# EasyEDA_SCH_5_5-OLED-to-RP5-MIPI-HAT.net
KiCad netlist of a schematic drawn in EasyEDA
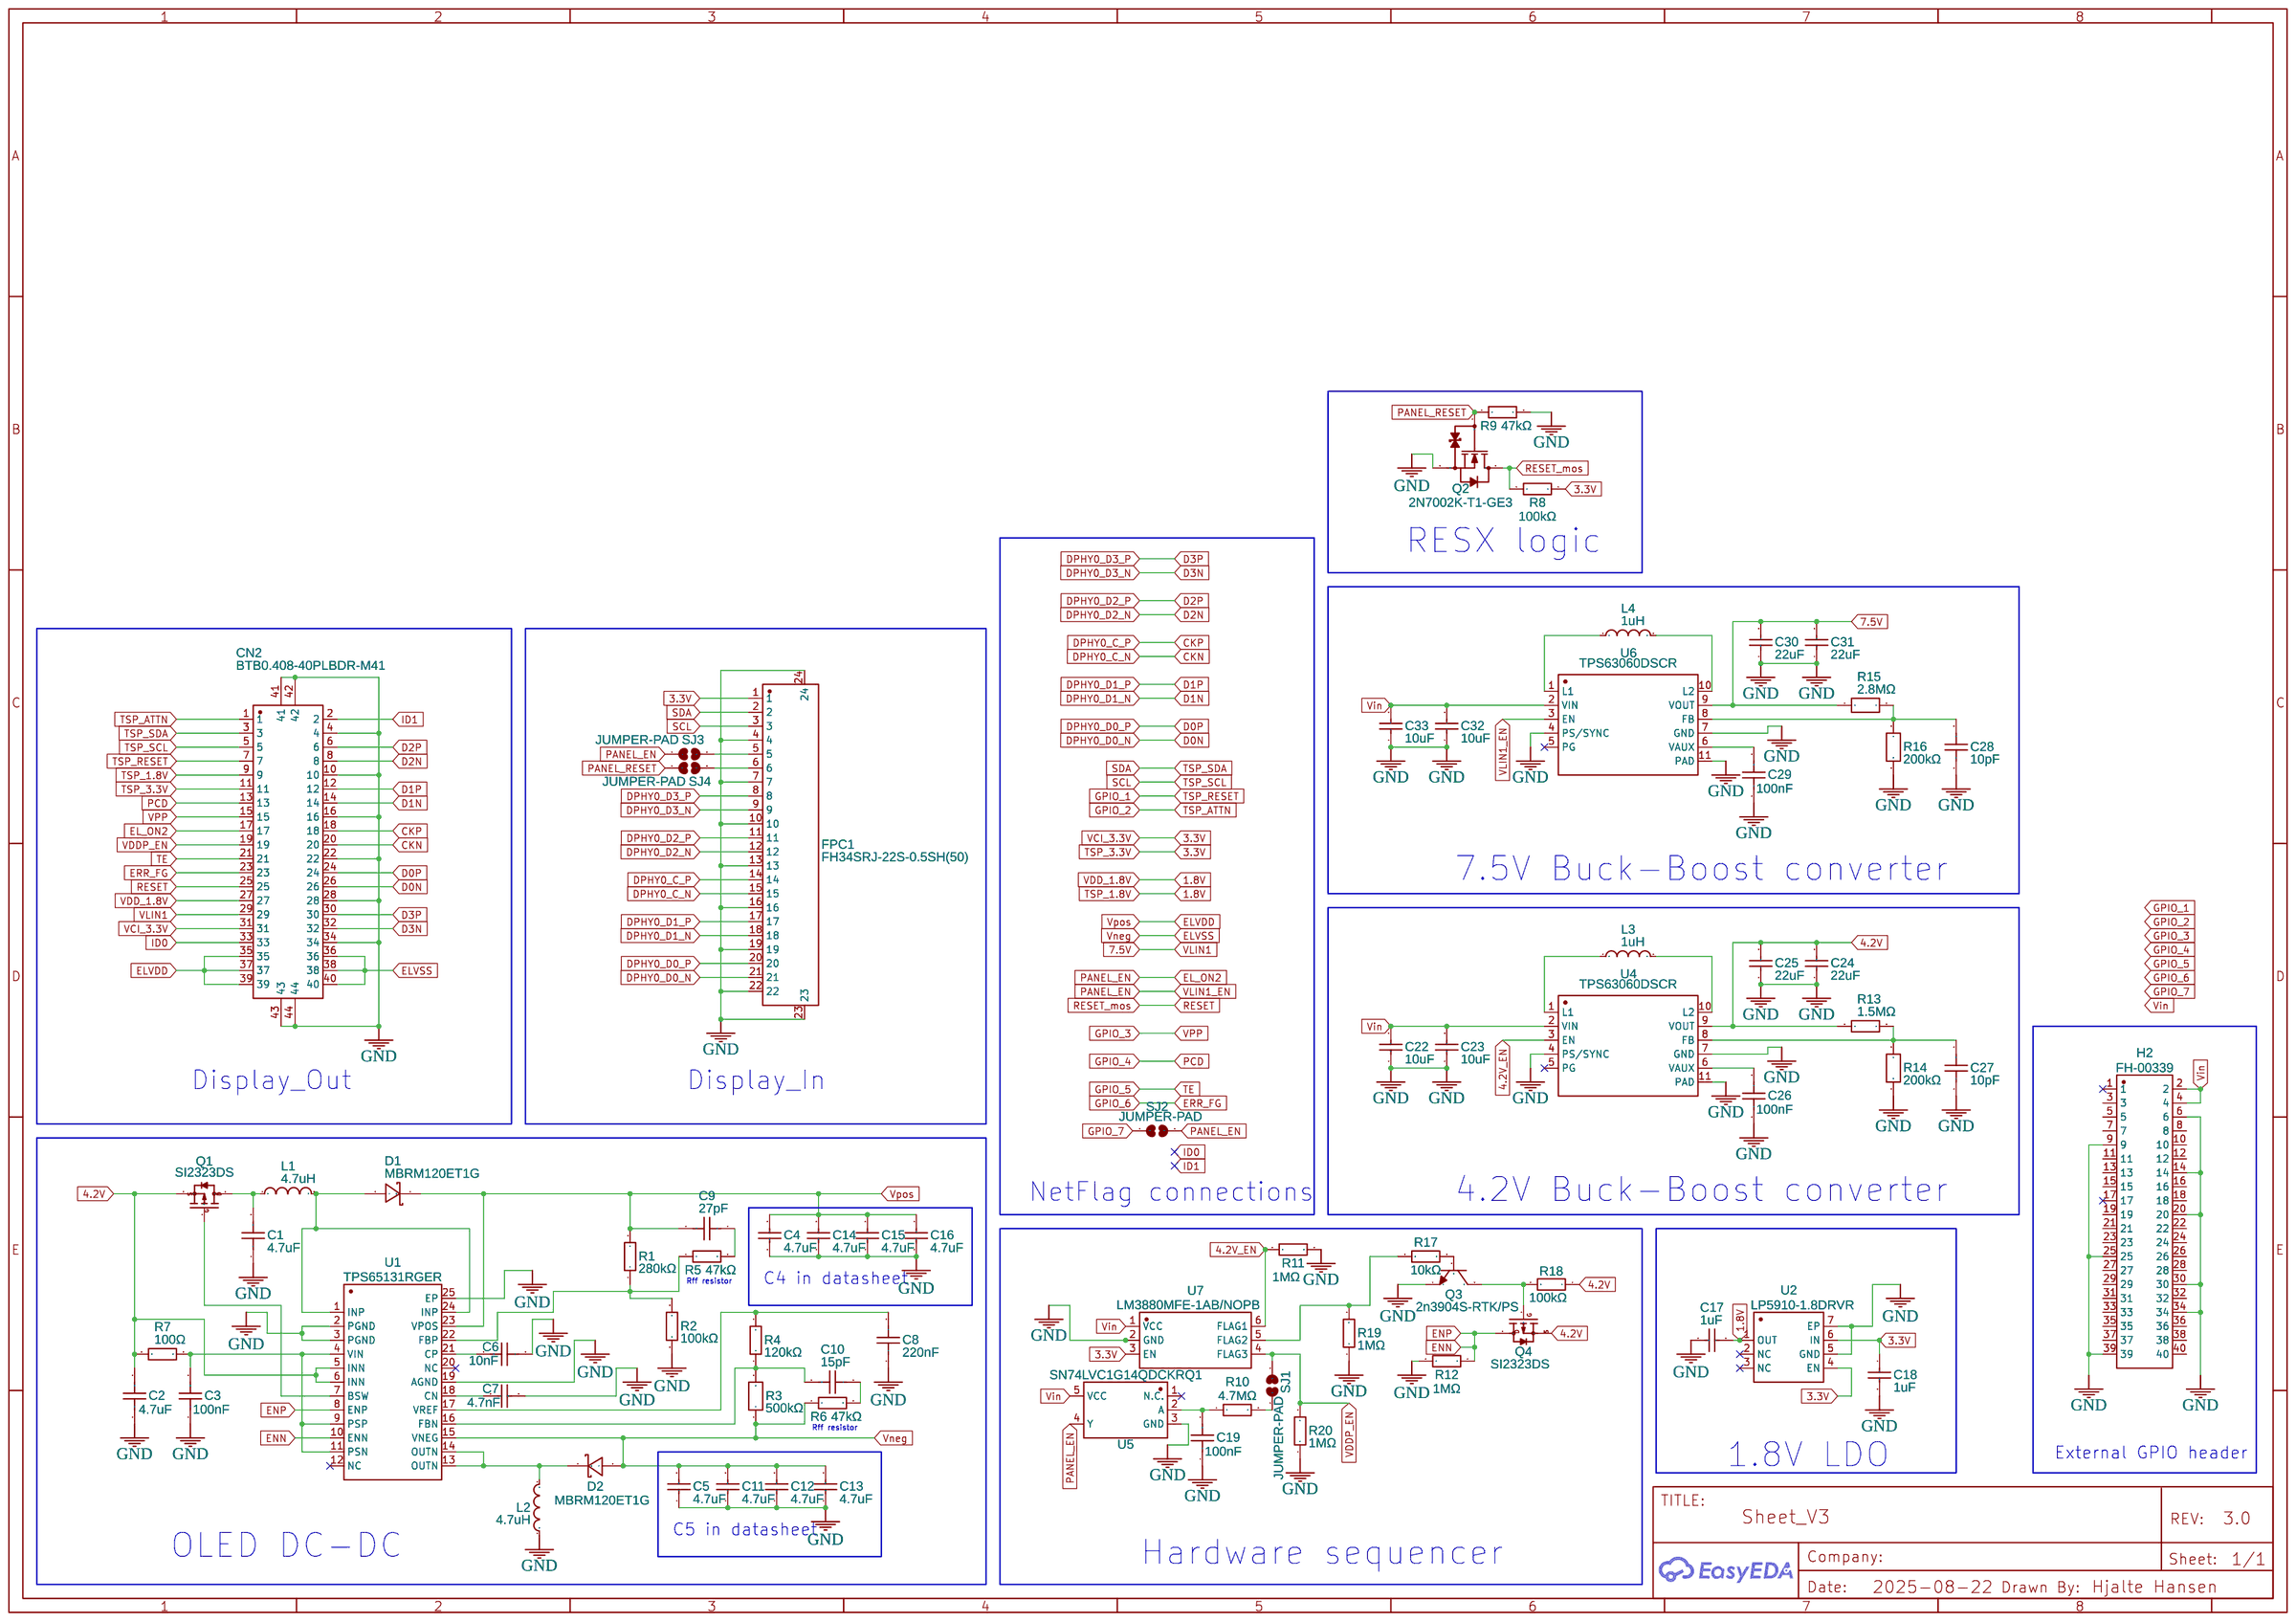
[diagram p0: schematic sheet]

(export (version "E")
  (design (tool "Eeschema 10.0.6"))
  (components
    (comp (ref "C1")
      (value "4.7uF")
      (fields
        (field (name "Manufacturer Part") "CL05A475MQ5NRNC")
        (field (name "Manufacturer") "SAMSUNG(三星)")
      )
      (libsource (lib "") (part "CL05A475MQ5NRNC_C307423"))
    )
    (comp (ref "C2")
      (value "4.7uF")
      (fields
        (field (name "Manufacturer Part") "CL05A475MQ5NRNC")
        (field (name "Manufacturer") "SAMSUNG(三星)")
      )
      (libsource (lib "") (part "CL05A475MQ5NRNC_C307423"))
    )
    (comp (ref "C3")
      (value "100nF")
      (fields
        (field (name "Manufacturer Part") "CL05B104KP5NNNC")
        (field (name "Manufacturer") "SAMSUNG(三星)")
      )
      (libsource (lib "") (part "CL05B104KP5NNNC"))
    )
    (comp (ref "C4")
      (value "4.7uF")
      (fields
        (field (name "Manufacturer Part") "CL21A475KAQNNNE")
        (field (name "Manufacturer") "SAMSUNG(三星)")
      )
      (libsource (lib "") (part "CL21A475KAQNNNE"))
    )
    (comp (ref "C5")
      (value "4.7uF")
      (fields
        (field (name "Manufacturer Part") "CL21A475KAQNNNE")
        (field (name "Manufacturer") "SAMSUNG(三星)")
      )
      (libsource (lib "") (part "CL21A475KAQNNNE"))
    )
    (comp (ref "C6")
      (value "10nF")
      (fields
        (field (name "Manufacturer Part") "CL05B103KO5NNNC")
        (field (name "Manufacturer") "SAMSUNG(三星)")
      )
      (libsource (lib "") (part "CL05B103KO5NNNC"))
    )
    (comp (ref "C7")
      (value "4.7nF")
      (fields
        (field (name "Manufacturer Part") "CL10B472KB8NNNC")
        (field (name "Manufacturer") "SAMSUNG(三星)")
      )
      (libsource (lib "") (part "CL10B472KB8NNNC"))
    )
    (comp (ref "C8")
      (value "220nF")
      (fields
        (field (name "Manufacturer Part") "CL05A224KQ5NNNC")
        (field (name "Manufacturer") "SAMSUNG(三星)")
      )
      (libsource (lib "") (part "CL05A224KQ5NNNC"))
    )
    (comp (ref "C9")
      (value "27pF")
      (fields
        (field (name "Manufacturer Part") "CC0603JRNPO7BN270")
        (field (name "Manufacturer") "YAGEO(国巨)")
      )
      (libsource (lib "") (part "CC0603JRNPO7BN270"))
    )
    (comp (ref "C10")
      (value "15pF")
      (fields
        (field (name "Manufacturer Part") "CC0402KRNPO7BN150")
        (field (name "Manufacturer") "YAGEO(国巨)")
      )
      (libsource (lib "") (part "CC0402KRNPO7BN150"))
    )
    (comp (ref "C11")
      (value "4.7uF")
      (fields
        (field (name "Manufacturer Part") "CL21A475KAQNNNE")
        (field (name "Manufacturer") "SAMSUNG(三星)")
      )
      (libsource (lib "") (part "CL21A475KAQNNNE"))
    )
    (comp (ref "C12")
      (value "4.7uF")
      (fields
        (field (name "Manufacturer Part") "CL21A475KAQNNNE")
        (field (name "Manufacturer") "SAMSUNG(三星)")
      )
      (libsource (lib "") (part "CL21A475KAQNNNE"))
    )
    (comp (ref "C13")
      (value "4.7uF")
      (fields
        (field (name "Manufacturer Part") "CL21A475KAQNNNE")
        (field (name "Manufacturer") "SAMSUNG(三星)")
      )
      (libsource (lib "") (part "CL21A475KAQNNNE"))
    )
    (comp (ref "C14")
      (value "4.7uF")
      (fields
        (field (name "Manufacturer Part") "CL21A475KAQNNNE")
        (field (name "Manufacturer") "SAMSUNG(三星)")
      )
      (libsource (lib "") (part "CL21A475KAQNNNE"))
    )
    (comp (ref "C15")
      (value "4.7uF")
      (fields
        (field (name "Manufacturer Part") "CL21A475KAQNNNE")
        (field (name "Manufacturer") "SAMSUNG(三星)")
      )
      (libsource (lib "") (part "CL21A475KAQNNNE"))
    )
    (comp (ref "C16")
      (value "4.7uF")
      (fields
        (field (name "Manufacturer Part") "CL21A475KAQNNNE")
        (field (name "Manufacturer") "SAMSUNG(三星)")
      )
      (libsource (lib "") (part "CL21A475KAQNNNE"))
    )
    (comp (ref "C17")
      (value "1uF")
      (fields
        (field (name "Manufacturer Part") "CL10A105KO8NNNC")
        (field (name "Manufacturer") "SAMSUNG(三星)")
      )
      (libsource (lib "") (part "CL10A105KO8NNNC_1"))
    )
    (comp (ref "C18")
      (value "1uF")
      (fields
        (field (name "Manufacturer Part") "CL10A105KO8NNNC")
        (field (name "Manufacturer") "SAMSUNG(三星)")
      )
      (libsource (lib "") (part "CL10A105KO8NNNC"))
    )
    (comp (ref "C19")
      (value "100nF")
      (fields
        (field (name "Manufacturer Part") "CL05B104KP5NNNC")
        (field (name "Manufacturer") "SAMSUNG(三星)")
      )
      (libsource (lib "") (part "CL05B104KP5NNNC"))
    )
    (comp (ref "C22")
      (value "10uF")
      (fields
        (field (name "Manufacturer Part") "CL21A106KOQNNNE")
        (field (name "Manufacturer") "SAMSUNG(三星)")
      )
      (libsource (lib "") (part "CL21A106KOQNNNE"))
    )
    (comp (ref "C23")
      (value "10uF")
      (fields
        (field (name "Manufacturer Part") "CL21A106KOQNNNE")
        (field (name "Manufacturer") "SAMSUNG(三星)")
      )
      (libsource (lib "") (part "CL21A106KOQNNNE"))
    )
    (comp (ref "C24")
      (value "22uF")
      (fields
        (field (name "Manufacturer Part") "CL21A226MOQNNNE")
        (field (name "Manufacturer") "SAMSUNG(三星)")
      )
      (libsource (lib "") (part "CL21A226MOQNNNE"))
    )
    (comp (ref "C25")
      (value "22uF")
      (fields
        (field (name "Manufacturer Part") "CL21A226MOQNNNE")
        (field (name "Manufacturer") "SAMSUNG(三星)")
      )
      (libsource (lib "") (part "CL21A226MOQNNNE"))
    )
    (comp (ref "C26")
      (value "100nF")
      (fields
        (field (name "Manufacturer Part") "CL05B104KP5NNNC")
        (field (name "Manufacturer") "SAMSUNG(三星)")
      )
      (libsource (lib "") (part "CL05B104KP5NNNC"))
    )
    (comp (ref "C27")
      (value "10pF")
      (fields
        (field (name "Manufacturer Part") "CL05C100JB5NNNC")
        (field (name "Manufacturer") "SAMSUNG(三星)")
      )
      (libsource (lib "") (part "CL05C100JB5NNNC"))
    )
    (comp (ref "C28")
      (value "10pF")
      (fields
        (field (name "Manufacturer Part") "CL05C100JB5NNNC")
        (field (name "Manufacturer") "SAMSUNG(三星)")
      )
      (libsource (lib "") (part "CL05C100JB5NNNC"))
    )
    (comp (ref "C29")
      (value "100nF")
      (fields
        (field (name "Manufacturer Part") "CL05B104KP5NNNC")
        (field (name "Manufacturer") "SAMSUNG(三星)")
      )
      (libsource (lib "") (part "CL05B104KP5NNNC"))
    )
    (comp (ref "C30")
      (value "22uF")
      (fields
        (field (name "Manufacturer Part") "CL21A226MOQNNNE")
        (field (name "Manufacturer") "SAMSUNG(三星)")
      )
      (libsource (lib "") (part "CL21A226MOQNNNE"))
    )
    (comp (ref "C31")
      (value "22uF")
      (fields
        (field (name "Manufacturer Part") "CL21A226MOQNNNE")
        (field (name "Manufacturer") "SAMSUNG(三星)")
      )
      (libsource (lib "") (part "CL21A226MOQNNNE"))
    )
    (comp (ref "C32")
      (value "10uF")
      (fields
        (field (name "Manufacturer Part") "CL21A106KOQNNNE")
        (field (name "Manufacturer") "SAMSUNG(三星)")
      )
      (libsource (lib "") (part "CL21A106KOQNNNE"))
    )
    (comp (ref "C33")
      (value "10uF")
      (fields
        (field (name "Manufacturer Part") "CL21A106KOQNNNE")
        (field (name "Manufacturer") "SAMSUNG(三星)")
      )
      (libsource (lib "") (part "CL21A106KOQNNNE"))
    )
    (comp (ref "CN2")
      (value "BTB0.408-40PLBDR-M41")
      (fields (field (name "Manufacturer") "XUNPU(讯普)"))
      (libsource (lib "") (part "BTB0.408-40PLBDR-M41"))
    )
    (comp (ref "D1")
      (value "MBRM120ET1G")
      (fields (field (name "Manufacturer") "onsemi(安森美)"))
      (libsource (lib "") (part "MBRM120ET1G_1"))
    )
    (comp (ref "D2")
      (value "MBRM120ET1G")
      (fields (field (name "Manufacturer") "onsemi(安森美)"))
      (libsource (lib "") (part "MBRM120ET1G"))
    )
    (comp (ref "FPC1")
      (value "FH34SRJ-22S-0.5SH(50)")
      (fields (field (name "Manufacturer") "HRS(广濑)"))
      (libsource (lib "") (part "FH34SRJ-22S-0.5SH(50)"))
    )
    (comp (ref "H2")
      (value "FH-00339")
      (fields (field (name "Manufacturer") "Liansheng(连盛)"))
      (libsource (lib "") (part "FH-00339"))
    )
    (comp (ref "L1")
      (value "4.7uH")
      (fields (field (name "Manufacturer Part") "FNR4020S4R7MT") (field (name "Manufacturer") "cjiang(长江微电)"))
      (libsource (lib "") (part "FNR4020S4R7MT"))
    )
    (comp (ref "L2")
      (value "4.7uH")
      (fields (field (name "Manufacturer Part") "FNR4020S4R7MT") (field (name "Manufacturer") "cjiang(长江微电)"))
      (libsource (lib "") (part "FNR4020S4R7MT_1"))
    )
    (comp (ref "L3")
      (value "1uH")
      (fields (field (name "Manufacturer Part") "MDA4020-1R0M") (field (name "Manufacturer") "KOHERelec(科或)"))
      (libsource (lib "") (part "MDA4020-1R0M"))
    )
    (comp (ref "L4")
      (value "1uH")
      (fields (field (name "Manufacturer Part") "MDA4020-1R0M") (field (name "Manufacturer") "KOHERelec(科或)"))
      (libsource (lib "") (part "MDA4020-1R0M"))
    )
    (comp (ref "Q1")
      (value "SI2323DS")
      (fields (field (name "Manufacturer") "TECH PUBLIC(台舟)"))
      (libsource (lib "") (part "SI2323DS_1"))
    )
    (comp (ref "Q2")
      (value "2N7002K-T1-GE3")
      (fields (field (name "Manufacturer") "VISHAY(威世)"))
      (libsource (lib "") (part "2N7002K-T1-GE3"))
    )
    (comp (ref "Q3")
      (value "2n3904S-RTK/PS")
      (fields (field (name "Manufacturer Part") "2N3904S-RTK/PS") (field (name "Manufacturer") "KEC"))
      (libsource (lib "") (part "2n3904S-RTK/PS_C18536"))
    )
    (comp (ref "Q4")
      (value "SI2323DS")
      (fields (field (name "Manufacturer") "TECH PUBLIC(台舟)"))
      (libsource (lib "") (part "SI2323DS"))
    )
    (comp (ref "R1")
      (value "280kΩ")
      (fields
        (field (name "Manufacturer Part") "0603WAF2803T5E")
        (field (name "Manufacturer") "UNI-ROYAL(厚声)")
      )
      (libsource (lib "") (part "0603WAF2803T5E"))
    )
    (comp (ref "R2")
      (value "100kΩ")
      (fields
        (field (name "Manufacturer Part") "0603WAF1003T5E")
        (field (name "Manufacturer") "UNI-ROYAL(厚声)")
      )
      (libsource (lib "") (part "0603WAF1003T5E"))
    )
    (comp (ref "R3")
      (value "500kΩ")
      (fields (field (name "Manufacturer Part") "AR03BTCX5003N") (field (name "Manufacturer") "Viking(光颉)"))
      (libsource (lib "") (part "AR03BTCX5003N"))
    )
    (comp (ref "R4")
      (value "120kΩ")
      (fields
        (field (name "Manufacturer Part") "0603WAF1203T5E")
        (field (name "Manufacturer") "UNI-ROYAL(厚声)")
      )
      (libsource (lib "") (part "0603WAF1203T5E"))
    )
    (comp (ref "R5")
      (value "47kΩ")
      (fields (field (name "Manufacturer Part") "RC0603FR-0747KL") (field (name "Manufacturer") "YAGEO(国巨)"))
      (libsource (lib "") (part "RC0603FR-0747KL"))
    )
    (comp (ref "R6")
      (value "47kΩ")
      (fields (field (name "Manufacturer Part") "RC0603FR-0747KL") (field (name "Manufacturer") "YAGEO(国巨)"))
      (libsource (lib "") (part "RC0603FR-0747KL"))
    )
    (comp (ref "R7")
      (value "100Ω")
      (fields (field (name "Manufacturer Part") "RC0402FR-07100RL") (field (name "Manufacturer") "YAGEO(国巨)"))
      (libsource (lib "") (part "RC0402FR-07100RL"))
    )
    (comp (ref "R8")
      (value "100kΩ")
      (fields (field (name "Manufacturer Part") "RC0603FR-07100KL") (field (name "Manufacturer") "YAGEO(国巨)"))
      (libsource (lib "") (part "RC0603FR-07100KL"))
    )
    (comp (ref "R9")
      (value "47kΩ")
      (fields (field (name "Manufacturer Part") "RC0603FR-0747KL") (field (name "Manufacturer") "YAGEO(国巨)"))
      (libsource (lib "") (part "RC0603FR-0747KL"))
    )
    (comp (ref "R10")
      (value "4.7MΩ")
      (fields
        (field (name "Manufacturer Part") "0603WAF4704T5E")
        (field (name "Manufacturer") "UNI-ROYAL(厚声)")
      )
      (libsource (lib "") (part "0603WAF4704T5E"))
    )
    (comp (ref "R11")
      (value "1MΩ")
      (fields (field (name "Manufacturer Part") "RC0603FR-071ML") (field (name "Manufacturer") "YAGEO(国巨)"))
      (libsource (lib "") (part "RC0603FR-071ML_1"))
    )
    (comp (ref "R12")
      (value "1MΩ")
      (fields (field (name "Manufacturer Part") "RC0603FR-071ML") (field (name "Manufacturer") "YAGEO(国巨)"))
      (libsource (lib "") (part "RC0603FR-071ML_2"))
    )
    (comp (ref "R13")
      (value "1.5MΩ")
      (fields (field (name "Manufacturer Part") "RC0603FR-071M5L") (field (name "Manufacturer") "YAGEO(国巨)"))
      (libsource (lib "") (part "RC0603FR-071M5L"))
    )
    (comp (ref "R14")
      (value "200kΩ")
      (fields (field (name "Manufacturer Part") "FRC0805F2003TS") (field (name "Manufacturer") "FOJAN(富捷)"))
      (libsource (lib "") (part "FRC0805F2003TS"))
    )
    (comp (ref "R15")
      (value "2.8MΩ")
      (fields (field (name "Manufacturer Part") "RC0603FR-072M8L") (field (name "Manufacturer") "YAGEO(国巨)"))
      (libsource (lib "") (part "RC0603FR-072M8L"))
    )
    (comp (ref "R16")
      (value "200kΩ")
      (fields (field (name "Manufacturer Part") "FRC0805F2003TS") (field (name "Manufacturer") "FOJAN(富捷)"))
      (libsource (lib "") (part "FRC0805F2003TS"))
    )
    (comp (ref "R17")
      (value "10kΩ")
      (fields (field (name "Manufacturer Part") "RC0603FR-0710KL") (field (name "Manufacturer") "YAGEO(国巨)"))
      (libsource (lib "") (part "RC0603FR-0710KL"))
    )
    (comp (ref "R18")
      (value "100kΩ")
      (fields (field (name "Manufacturer Part") "RC0603FR-07100KL") (field (name "Manufacturer") "YAGEO(国巨)"))
      (libsource (lib "") (part "RC0603FR-07100KL"))
    )
    (comp (ref "R19")
      (value "1MΩ")
      (fields (field (name "Manufacturer Part") "RC0603FR-071ML") (field (name "Manufacturer") "YAGEO(国巨)"))
      (libsource (lib "") (part "RC0603FR-071ML"))
    )
    (comp (ref "R20")
      (value "1MΩ")
      (fields (field (name "Manufacturer Part") "RC0603FR-071ML") (field (name "Manufacturer") "YAGEO(国巨)"))
      (libsource (lib "") (part "RC0603FR-071ML"))
    )
    (comp (ref "SJ1") (value "JUMPER-PAD") (libsource (lib "") (part "JUMPER-PAD_1")))
    (comp (ref "SJ2") (value "JUMPER-PAD") (libsource (lib "") (part "JUMPER-PAD")))
    (comp (ref "SJ3") (value "JUMPER-PAD") (libsource (lib "") (part "JUMPER-PAD")))
    (comp (ref "SJ4") (value "JUMPER-PAD") (libsource (lib "") (part "JUMPER-PAD")))
    (comp (ref "U1")
      (value "TPS65131RGER")
      (fields (field (name "Manufacturer") "TI(德州仪器)"))
      (libsource (lib "") (part "TPS65131RGER"))
    )
    (comp (ref "U2")
      (value "LP5910-1.8DRVR")
      (fields (field (name "Manufacturer") "TI(德州仪器)"))
      (libsource (lib "") (part "LP5910-1.8DRVR"))
    )
    (comp (ref "U4")
      (value "TPS63060DSCR")
      (fields (field (name "Manufacturer") "TI(德州仪器)"))
      (libsource (lib "") (part "TPS63060DSCR"))
    )
    (comp (ref "U5")
      (value "SN74LVC1G14QDCKRQ1")
      (fields (field (name "Manufacturer") "TI(德州仪器)"))
      (libsource (lib "") (part "SN74LVC1G14QDCKRQ1"))
    )
    (comp (ref "U6")
      (value "TPS63060DSCR")
      (fields (field (name "Manufacturer") "TI(德州仪器)"))
      (libsource (lib "") (part "TPS63060DSCR"))
    )
    (comp (ref "U7")
      (value "LM3880MFE-1AB/NOPB")
      (fields (field (name "Manufacturer") "TI(德州仪器)"))
      (libsource (lib "") (part "LM3880MFE-1AB/NOPB"))
    )
  )
  (nets
    (net (code "1") (name "1.8V") (class "Default")
      (node (ref "C17") (pin "1") (pinfunction "1_1") (pintype "input"))
      (node (ref "CN2") (pin "27") (pinfunction "27_27") (pintype "unspecified"))
      (node (ref "CN2") (pin "9") (pinfunction "9_9") (pintype "unspecified"))
      (node (ref "U2") (pin "1") (pinfunction "OUT_1") (pintype "unspecified"))
    )
    (net (code "2") (name "3.3V") (class "Default")
      (node (ref "C18") (pin "1") (pinfunction "1_1") (pintype "input"))
      (node (ref "CN2") (pin "11") (pinfunction "11_11") (pintype "unspecified"))
      (node (ref "CN2") (pin "31") (pinfunction "31_31") (pintype "unspecified"))
      (node (ref "FPC1") (pin "1") (pinfunction "1_1") (pintype "unspecified"))
      (node (ref "R8") (pin "1") (pinfunction "1_1") (pintype "unspecified"))
      (node (ref "U2") (pin "4") (pinfunction "EN_4") (pintype "unspecified"))
      (node (ref "U2") (pin "6") (pinfunction "IN_6") (pintype "unspecified"))
      (node (ref "U7") (pin "3") (pinfunction "EN_3") (pintype "unspecified"))
    )
    (net (code "3") (name "4.2V") (class "Default")
      (node (ref "C2") (pin "2") (pinfunction "2_2") (pintype "unspecified"))
      (node (ref "C24") (pin "2") (pinfunction "2_2") (pintype "input"))
      (node (ref "C25") (pin "2") (pinfunction "2_2") (pintype "input"))
      (node (ref "Q1") (pin "2") (pinfunction "S_2") (pintype "unspecified"))
      (node (ref "Q4") (pin "2") (pinfunction "S_2") (pintype "unspecified"))
      (node (ref "R13") (pin "1") (pinfunction "1_1") (pintype "input"))
      (node (ref "R18") (pin "1") (pinfunction "1_1") (pintype "unspecified"))
      (node (ref "R7") (pin "1") (pinfunction "1_1") (pintype "input"))
      (node (ref "U1") (pin "5") (pinfunction "INN_5") (pintype "unspecified"))
      (node (ref "U1") (pin "6") (pinfunction "INN_6") (pintype "unspecified"))
      (node (ref "U4") (pin "9") (pinfunction "VOUT_9") (pintype "unspecified"))
    )
    (net (code "4") (name "4.2V_EN") (class "Default")
      (node (ref "R11") (pin "1") (pinfunction "1_1") (pintype "input"))
      (node (ref "U4") (pin "3") (pinfunction "EN_3") (pintype "unspecified"))
      (node (ref "U7") (pin "6") (pinfunction "FLAG1_6") (pintype "unspecified"))
    )
    (net (code "5") (name "7.5V") (class "Default")
      (node (ref "C30") (pin "2") (pinfunction "2_2") (pintype "input"))
      (node (ref "C31") (pin "2") (pinfunction "2_2") (pintype "input"))
      (node (ref "CN2") (pin "29") (pinfunction "29_29") (pintype "unspecified"))
      (node (ref "R15") (pin "1") (pinfunction "1_1") (pintype "unspecified"))
      (node (ref "U6") (pin "9") (pinfunction "VOUT_9") (pintype "unspecified"))
    )
    (net (code "6") (name "CKN") (class "Default")
      (node (ref "CN2") (pin "20") (pinfunction "20_20") (pintype "unspecified"))
      (node (ref "FPC1") (pin "15") (pinfunction "15_15") (pintype "unspecified"))
    )
    (net (code "7") (name "CKP") (class "Default")
      (node (ref "CN2") (pin "18") (pinfunction "18_18") (pintype "unspecified"))
      (node (ref "FPC1") (pin "14") (pinfunction "14_14") (pintype "unspecified"))
    )
    (net (code "8") (name "D0N") (class "Default")
      (node (ref "CN2") (pin "26") (pinfunction "26_26") (pintype "unspecified"))
      (node (ref "FPC1") (pin "21") (pinfunction "21_21") (pintype "unspecified"))
    )
    (net (code "9") (name "D0P") (class "Default")
      (node (ref "CN2") (pin "24") (pinfunction "24_24") (pintype "unspecified"))
      (node (ref "FPC1") (pin "20") (pinfunction "20_20") (pintype "unspecified"))
    )
    (net (code "10") (name "D1N") (class "Default")
      (node (ref "CN2") (pin "14") (pinfunction "14_14") (pintype "unspecified"))
      (node (ref "FPC1") (pin "18") (pinfunction "18_18") (pintype "unspecified"))
    )
    (net (code "11") (name "D1P") (class "Default")
      (node (ref "CN2") (pin "12") (pinfunction "12_12") (pintype "unspecified"))
      (node (ref "FPC1") (pin "17") (pinfunction "17_17") (pintype "unspecified"))
    )
    (net (code "12") (name "D2N") (class "Default")
      (node (ref "CN2") (pin "8") (pinfunction "8_8") (pintype "unspecified"))
      (node (ref "FPC1") (pin "12") (pinfunction "12_12") (pintype "unspecified"))
    )
    (net (code "13") (name "D2P") (class "Default")
      (node (ref "CN2") (pin "6") (pinfunction "6_6") (pintype "unspecified"))
      (node (ref "FPC1") (pin "11") (pinfunction "11_11") (pintype "unspecified"))
    )
    (net (code "14") (name "D3N") (class "Default")
      (node (ref "CN2") (pin "32") (pinfunction "32_32") (pintype "unspecified"))
      (node (ref "FPC1") (pin "9") (pinfunction "9_9") (pintype "unspecified"))
    )
    (net (code "15") (name "D3P") (class "Default")
      (node (ref "CN2") (pin "30") (pinfunction "30_30") (pintype "unspecified"))
      (node (ref "FPC1") (pin "8") (pinfunction "8_8") (pintype "unspecified"))
    )
    (net (code "16") (name "ELVDD") (class "Default")
      (node (ref "C14") (pin "2") (pinfunction "2_2") (pintype "input"))
      (node (ref "C15") (pin "2") (pinfunction "2_2") (pintype "input"))
      (node (ref "C16") (pin "2") (pinfunction "2_2") (pintype "input"))
      (node (ref "C4") (pin "2") (pinfunction "2_2") (pintype "input"))
      (node (ref "C9") (pin "2") (pinfunction "2_2") (pintype "unspecified"))
      (node (ref "CN2") (pin "35") (pinfunction "35_35") (pintype "unspecified"))
      (node (ref "CN2") (pin "37") (pinfunction "37_37") (pintype "unspecified"))
      (node (ref "CN2") (pin "39") (pinfunction "39_39") (pintype "unspecified"))
      (node (ref "D1") (pin "1") (pinfunction "C_1") (pintype "unspecified"))
      (node (ref "R1") (pin "2") (pinfunction "2_2") (pintype "input"))
      (node (ref "U1") (pin "23") (pinfunction "VPOS_23") (pintype "unspecified"))
    )
    (net (code "17") (name "ELVSS") (class "Default")
      (node (ref "C11") (pin "2") (pinfunction "2_2") (pintype "input"))
      (node (ref "C12") (pin "2") (pinfunction "2_2") (pintype "input"))
      (node (ref "C13") (pin "2") (pinfunction "2_2") (pintype "input"))
      (node (ref "C5") (pin "2") (pinfunction "2_2") (pintype "input"))
      (node (ref "CN2") (pin "36") (pinfunction "36_36") (pintype "unspecified"))
      (node (ref "CN2") (pin "38") (pinfunction "38_38") (pintype "unspecified"))
      (node (ref "CN2") (pin "40") (pinfunction "40_40") (pintype "unspecified"))
      (node (ref "D2") (pin "2") (pinfunction "A_2") (pintype "unspecified"))
      (node (ref "R3") (pin "1") (pinfunction "1_1") (pintype "unspecified"))
      (node (ref "R6") (pin "1") (pinfunction "1_1") (pintype "input"))
      (node (ref "U1") (pin "15") (pinfunction "VNEG_15") (pintype "unspecified"))
    )
    (net (code "18") (name "EL_ON2") (class "Default")
      (node (ref "CN2") (pin "17") (pinfunction "17_17") (pintype "unspecified"))
      (node (ref "SJ2") (pin "2") (pinfunction "2_2") (pintype "unspecified"))
      (node (ref "SJ3") (pin "1") (pinfunction "1_1") (pintype "unspecified"))
      (node (ref "U5") (pin "4") (pinfunction "Y_4") (pintype "unspecified"))
      (node (ref "U6") (pin "3") (pinfunction "EN_3") (pintype "unspecified"))
    )
    (net (code "19") (name "ENN") (class "Default")
      (node (ref "Q4") (pin "3") (pinfunction "D_3") (pintype "unspecified"))
      (node (ref "R12") (pin "1") (pinfunction "1_1") (pintype "input"))
      (node (ref "U1") (pin "10") (pinfunction "ENN_10") (pintype "unspecified"))
      (node (ref "U1") (pin "8") (pinfunction "ENP_8") (pintype "unspecified"))
    )
    (net (code "20") (name "ERR_FG") (class "Default")
      (node (ref "CN2") (pin "23") (pinfunction "23_23") (pintype "unspecified"))
    )
    (net (code "21") (name "GND") (class "Default")
      (node (ref "C1") (pin "1") (pinfunction "1_1") (pintype "unspecified"))
      (node (ref "C11") (pin "1") (pinfunction "1_1") (pintype "input"))
      (node (ref "C12") (pin "1") (pinfunction "1_1") (pintype "input"))
      (node (ref "C13") (pin "1") (pinfunction "1_1") (pintype "input"))
      (node (ref "C14") (pin "1") (pinfunction "1_1") (pintype "input"))
      (node (ref "C15") (pin "1") (pinfunction "1_1") (pintype "input"))
      (node (ref "C16") (pin "1") (pinfunction "1_1") (pintype "input"))
      (node (ref "C17") (pin "2") (pinfunction "2_2") (pintype "input"))
      (node (ref "C18") (pin "2") (pinfunction "2_2") (pintype "input"))
      (node (ref "C19") (pin "1") (pinfunction "1_1") (pintype "unspecified"))
      (node (ref "C2") (pin "1") (pinfunction "1_1") (pintype "unspecified"))
      (node (ref "C22") (pin "1") (pinfunction "1_1") (pintype "input"))
      (node (ref "C23") (pin "1") (pinfunction "1_1") (pintype "input"))
      (node (ref "C24") (pin "1") (pinfunction "1_1") (pintype "input"))
      (node (ref "C25") (pin "1") (pinfunction "1_1") (pintype "input"))
      (node (ref "C26") (pin "1") (pinfunction "1_1") (pintype "unspecified"))
      (node (ref "C27") (pin "1") (pinfunction "1_1") (pintype "unspecified"))
      (node (ref "C28") (pin "1") (pinfunction "1_1") (pintype "unspecified"))
      (node (ref "C29") (pin "1") (pinfunction "1_1") (pintype "unspecified"))
      (node (ref "C3") (pin "1") (pinfunction "1_1") (pintype "unspecified"))
      (node (ref "C30") (pin "1") (pinfunction "1_1") (pintype "input"))
      (node (ref "C31") (pin "1") (pinfunction "1_1") (pintype "input"))
      (node (ref "C32") (pin "1") (pinfunction "1_1") (pintype "input"))
      (node (ref "C33") (pin "1") (pinfunction "1_1") (pintype "input"))
      (node (ref "C4") (pin "1") (pinfunction "1_1") (pintype "input"))
      (node (ref "C5") (pin "1") (pinfunction "1_1") (pintype "input"))
      (node (ref "C6") (pin "2") (pinfunction "2_2") (pintype "unspecified"))
      (node (ref "C7") (pin "2") (pinfunction "2_2") (pintype "input"))
      (node (ref "C8") (pin "1") (pinfunction "1_1") (pintype "unspecified"))
      (node (ref "CN2") (pin "10") (pinfunction "10_10") (pintype "unspecified"))
      (node (ref "CN2") (pin "16") (pinfunction "16_16") (pintype "unspecified"))
      (node (ref "CN2") (pin "22") (pinfunction "22_22") (pintype "unspecified"))
      (node (ref "CN2") (pin "28") (pinfunction "28_28") (pintype "unspecified"))
      (node (ref "CN2") (pin "34") (pinfunction "34_34") (pintype "unspecified"))
      (node (ref "CN2") (pin "4") (pinfunction "4_4") (pintype "unspecified"))
      (node (ref "CN2") (pin "41") (pinfunction "41_41") (pintype "unspecified"))
      (node (ref "CN2") (pin "42") (pinfunction "42_42") (pintype "unspecified"))
      (node (ref "CN2") (pin "43") (pinfunction "43_43") (pintype "unspecified"))
      (node (ref "CN2") (pin "44") (pinfunction "44_44") (pintype "unspecified"))
      (node (ref "FPC1") (pin "10") (pinfunction "10_10") (pintype "unspecified"))
      (node (ref "FPC1") (pin "13") (pinfunction "13_13") (pintype "unspecified"))
      (node (ref "FPC1") (pin "16") (pinfunction "16_16") (pintype "unspecified"))
      (node (ref "FPC1") (pin "19") (pinfunction "19_19") (pintype "unspecified"))
      (node (ref "FPC1") (pin "22") (pinfunction "22_22") (pintype "unspecified"))
      (node (ref "FPC1") (pin "23") (pinfunction "23_23") (pintype "unspecified"))
      (node (ref "FPC1") (pin "24") (pinfunction "24_24") (pintype "unspecified"))
      (node (ref "FPC1") (pin "4") (pinfunction "4_4") (pintype "unspecified"))
      (node (ref "FPC1") (pin "7") (pinfunction "7_7") (pintype "unspecified"))
      (node (ref "H2") (pin "14") (pinfunction "14_14") (pintype "unspecified"))
      (node (ref "H2") (pin "20") (pinfunction "20_20") (pintype "unspecified"))
      (node (ref "H2") (pin "25") (pinfunction "25_25") (pintype "unspecified"))
      (node (ref "H2") (pin "30") (pinfunction "30_30") (pintype "unspecified"))
      (node (ref "H2") (pin "34") (pinfunction "34_34") (pintype "unspecified"))
      (node (ref "H2") (pin "39") (pinfunction "39_39") (pintype "unspecified"))
      (node (ref "H2") (pin "6") (pinfunction "6_6") (pintype "unspecified"))
      (node (ref "H2") (pin "9") (pinfunction "9_9") (pintype "unspecified"))
      (node (ref "L2") (pin "2") (pinfunction "2_2") (pintype "unspecified"))
      (node (ref "Q2") (pin "2") (pinfunction "S_2") (pintype "unspecified"))
      (node (ref "Q3") (pin "1") (pinfunction "E_1") (pintype "input"))
      (node (ref "R11") (pin "2") (pinfunction "2_2") (pintype "input"))
      (node (ref "R12") (pin "2") (pinfunction "2_2") (pintype "input"))
      (node (ref "R14") (pin "1") (pinfunction "1_1") (pintype "unspecified"))
      (node (ref "R16") (pin "1") (pinfunction "1_1") (pintype "unspecified"))
      (node (ref "R19") (pin "1") (pinfunction "1_1") (pintype "input"))
      (node (ref "R2") (pin "1") (pinfunction "1_1") (pintype "input"))
      (node (ref "R20") (pin "1") (pinfunction "1_1") (pintype "input"))
      (node (ref "R9") (pin "2") (pinfunction "2_2") (pintype "input"))
      (node (ref "U1") (pin "19") (pinfunction "AGND_19") (pintype "unspecified"))
      (node (ref "U1") (pin "2") (pinfunction "PGND_2") (pintype "unspecified"))
      (node (ref "U1") (pin "25") (pinfunction "EP_25") (pintype "unspecified"))
      (node (ref "U1") (pin "3") (pinfunction "PGND_3") (pintype "unspecified"))
      (node (ref "U2") (pin "5") (pinfunction "GND_5") (pintype "unspecified"))
      (node (ref "U2") (pin "7") (pinfunction "EP_7") (pintype "unspecified"))
      (node (ref "U4") (pin "11") (pinfunction "PAD_11") (pintype "unspecified"))
      (node (ref "U4") (pin "4") (pinfunction "PS/SYNC_4") (pintype "unspecified"))
      (node (ref "U4") (pin "7") (pinfunction "GND_7") (pintype "unspecified"))
      (node (ref "U5") (pin "3") (pinfunction "GND_3") (pintype "unspecified"))
      (node (ref "U6") (pin "11") (pinfunction "PAD_11") (pintype "unspecified"))
      (node (ref "U6") (pin "4") (pinfunction "PS/SYNC_4") (pintype "unspecified"))
      (node (ref "U6") (pin "7") (pinfunction "GND_7") (pintype "unspecified"))
      (node (ref "U7") (pin "2") (pinfunction "GND_2") (pintype "unspecified"))
    )
    (net (code "22") (name "GPIO_1") (class "Default")
      (node (ref "CN2") (pin "7") (pinfunction "7_7") (pintype "unspecified"))
    )
    (net (code "23") (name "GPIO_2") (class "Default")
      (node (ref "CN2") (pin "1") (pinfunction "1_1") (pintype "unspecified"))
    )
    (net (code "24") (name "GPIO_3") (class "Default")
      (node (ref "CN2") (pin "15") (pinfunction "15_15") (pintype "unspecified"))
    )
    (net (code "25") (name "GPIO_4") (class "Default")
      (node (ref "CN2") (pin "13") (pinfunction "13_13") (pintype "unspecified"))
    )
    (net (code "26") (name "GPIO_5") (class "Default")
      (node (ref "CN2") (pin "21") (pinfunction "21_21") (pintype "unspecified"))
    )
    (net (code "27") (name "GPIO_7") (class "Default")
      (node (ref "SJ2") (pin "1") (pinfunction "1_1") (pintype "unspecified"))
    )
    (net (code "28") (name "ID0") (class "Default")
      (node (ref "CN2") (pin "33") (pinfunction "33_33") (pintype "unspecified"))
    )
    (net (code "29") (name "ID1") (class "Default")
      (node (ref "CN2") (pin "2") (pinfunction "2_2") (pintype "unspecified"))
    )
    (net (code "30") (name "Net-(C9-Pad1)") (class "Default")
      (node (ref "C9") (pin "1") (pinfunction "1_1") (pintype "unspecified"))
      (node (ref "R5") (pin "2") (pinfunction "2_2") (pintype "input"))
    )
    (net (code "31") (name "Net-(C10-Pad1)") (class "Default")
      (node (ref "C10") (pin "1") (pinfunction "1_1") (pintype "unspecified"))
      (node (ref "R6") (pin "2") (pinfunction "2_2") (pintype "input"))
    )
    (net (code "32") (name "Net-(D1-A)") (class "Default")
      (node (ref "D1") (pin "2") (pinfunction "A_2") (pintype "unspecified"))
      (node (ref "L1") (pin "2") (pinfunction "2_2") (pintype "unspecified"))
      (node (ref "U1") (pin "1") (pinfunction "INP_1") (pintype "unspecified"))
      (node (ref "U1") (pin "24") (pinfunction "INP_24") (pintype "unspecified"))
    )
    (net (code "33") (name "Net-(D2-C)") (class "Default")
      (node (ref "D2") (pin "1") (pinfunction "C_1") (pintype "unspecified"))
      (node (ref "L2") (pin "1") (pinfunction "1_1") (pintype "unspecified"))
      (node (ref "U1") (pin "13") (pinfunction "OUTN_13") (pintype "unspecified"))
      (node (ref "U1") (pin "14") (pinfunction "OUTN_14") (pintype "unspecified"))
    )
    (net (code "34") (name "Net-(FPC1-Pad5)") (class "Default")
      (node (ref "FPC1") (pin "5") (pinfunction "5_5") (pintype "unspecified"))
      (node (ref "SJ3") (pin "2") (pinfunction "2_2") (pintype "unspecified"))
    )
    (net (code "35") (name "Net-(FPC1-Pad6)") (class "Default")
      (node (ref "FPC1") (pin "6") (pinfunction "6_6") (pintype "unspecified"))
      (node (ref "SJ4") (pin "2") (pinfunction "2_2") (pintype "unspecified"))
    )
    (net (code "36") (name "Net-(Q1-D)") (class "Default")
      (node (ref "C1") (pin "2") (pinfunction "2_2") (pintype "unspecified"))
      (node (ref "L1") (pin "1") (pinfunction "1_1") (pintype "unspecified"))
      (node (ref "Q1") (pin "3") (pinfunction "D_3") (pintype "unspecified"))
    )
    (net (code "37") (name "Net-(Q1-G)") (class "Default")
      (node (ref "Q1") (pin "1") (pinfunction "G_1") (pintype "unspecified"))
      (node (ref "U1") (pin "7") (pinfunction "BSW_7") (pintype "unspecified"))
    )
    (net (code "38") (name "Net-(Q3-B)") (class "Default")
      (node (ref "Q3") (pin "2") (pinfunction "B_2") (pintype "input"))
      (node (ref "R17") (pin "2") (pinfunction "2_2") (pintype "input"))
    )
    (net (code "39") (name "Net-(Q3-C)") (class "Default")
      (node (ref "Q3") (pin "3") (pinfunction "C_3") (pintype "input"))
      (node (ref "Q4") (pin "1") (pinfunction "G_1") (pintype "unspecified"))
      (node (ref "R18") (pin "2") (pinfunction "2_2") (pintype "unspecified"))
    )
    (net (code "40") (name "Net-(R10-Pad2)") (class "Default")
      (node (ref "R10") (pin "2") (pinfunction "2_2") (pintype "input"))
      (node (ref "SJ1") (pin "1") (pinfunction "1_1") (pintype "unspecified"))
    )
    (net (code "41") (name "Net-(U1-CN)") (class "Default")
      (node (ref "C7") (pin "1") (pinfunction "1_1") (pintype "input"))
      (node (ref "U1") (pin "18") (pinfunction "CN_18") (pintype "unspecified"))
    )
    (net (code "42") (name "Net-(U1-CP)") (class "Default")
      (node (ref "C6") (pin "1") (pinfunction "1_1") (pintype "unspecified"))
      (node (ref "U1") (pin "21") (pinfunction "CP_21") (pintype "unspecified"))
    )
    (net (code "43") (name "Net-(U1-FBN)") (class "Default")
      (node (ref "C10") (pin "2") (pinfunction "2_2") (pintype "unspecified"))
      (node (ref "R3") (pin "2") (pinfunction "2_2") (pintype "unspecified"))
      (node (ref "R4") (pin "1") (pinfunction "1_1") (pintype "input"))
      (node (ref "U1") (pin "16") (pinfunction "FBN_16") (pintype "unspecified"))
    )
    (net (code "44") (name "Net-(U1-FBP)") (class "Default")
      (node (ref "R1") (pin "1") (pinfunction "1_1") (pintype "input"))
      (node (ref "R2") (pin "2") (pinfunction "2_2") (pintype "input"))
      (node (ref "R5") (pin "1") (pinfunction "1_1") (pintype "input"))
      (node (ref "U1") (pin "22") (pinfunction "FBP_22") (pintype "unspecified"))
    )
    (net (code "45") (name "Net-(U1-PSN)") (class "Default")
      (node (ref "C3") (pin "2") (pinfunction "2_2") (pintype "unspecified"))
      (node (ref "R7") (pin "2") (pinfunction "2_2") (pintype "input"))
      (node (ref "U1") (pin "11") (pinfunction "PSN_11") (pintype "unspecified"))
      (node (ref "U1") (pin "4") (pinfunction "VIN_4") (pintype "unspecified"))
      (node (ref "U1") (pin "9") (pinfunction "PSP_9") (pintype "unspecified"))
    )
    (net (code "46") (name "Net-(U1-VREF)") (class "Default")
      (node (ref "C8") (pin "2") (pinfunction "2_2") (pintype "unspecified"))
      (node (ref "R4") (pin "2") (pinfunction "2_2") (pintype "input"))
      (node (ref "U1") (pin "17") (pinfunction "VREF_17") (pintype "unspecified"))
    )
    (net (code "47") (name "Net-(U4-FB)") (class "Default")
      (node (ref "C27") (pin "2") (pinfunction "2_2") (pintype "unspecified"))
      (node (ref "R13") (pin "2") (pinfunction "2_2") (pintype "input"))
      (node (ref "R14") (pin "2") (pinfunction "2_2") (pintype "unspecified"))
      (node (ref "U4") (pin "8") (pinfunction "FB_8") (pintype "unspecified"))
    )
    (net (code "48") (name "Net-(U4-L1)") (class "Default")
      (node (ref "L3") (pin "1") (pinfunction "1_1") (pintype "unspecified"))
      (node (ref "U4") (pin "1") (pinfunction "L1_1") (pintype "unspecified"))
    )
    (net (code "49") (name "Net-(U4-L2)") (class "Default")
      (node (ref "L3") (pin "2") (pinfunction "2_2") (pintype "unspecified"))
      (node (ref "U4") (pin "10") (pinfunction "L2_10") (pintype "unspecified"))
    )
    (net (code "50") (name "Net-(U4-VAUX)") (class "Default")
      (node (ref "C26") (pin "2") (pinfunction "2_2") (pintype "unspecified"))
      (node (ref "U4") (pin "6") (pinfunction "VAUX_6") (pintype "unspecified"))
    )
    (net (code "51") (name "Net-(U5-A)") (class "Default")
      (node (ref "C19") (pin "2") (pinfunction "2_2") (pintype "unspecified"))
      (node (ref "R10") (pin "1") (pinfunction "1_1") (pintype "input"))
      (node (ref "U5") (pin "2") (pinfunction "A_2") (pintype "unspecified"))
    )
    (net (code "52") (name "Net-(U6-FB)") (class "Default")
      (node (ref "C28") (pin "2") (pinfunction "2_2") (pintype "unspecified"))
      (node (ref "R15") (pin "2") (pinfunction "2_2") (pintype "unspecified"))
      (node (ref "R16") (pin "2") (pinfunction "2_2") (pintype "unspecified"))
      (node (ref "U6") (pin "8") (pinfunction "FB_8") (pintype "unspecified"))
    )
    (net (code "53") (name "Net-(U6-L1)") (class "Default")
      (node (ref "L4") (pin "1") (pinfunction "1_1") (pintype "unspecified"))
      (node (ref "U6") (pin "1") (pinfunction "L1_1") (pintype "unspecified"))
    )
    (net (code "54") (name "Net-(U6-L2)") (class "Default")
      (node (ref "L4") (pin "2") (pinfunction "2_2") (pintype "unspecified"))
      (node (ref "U6") (pin "10") (pinfunction "L2_10") (pintype "unspecified"))
    )
    (net (code "55") (name "Net-(U6-VAUX)") (class "Default")
      (node (ref "C29") (pin "2") (pinfunction "2_2") (pintype "unspecified"))
      (node (ref "U6") (pin "6") (pinfunction "VAUX_6") (pintype "unspecified"))
    )
    (net (code "56") (name "Net-(U7-FLAG2)") (class "Default")
      (node (ref "R17") (pin "1") (pinfunction "1_1") (pintype "input"))
      (node (ref "R19") (pin "2") (pinfunction "2_2") (pintype "input"))
      (node (ref "U7") (pin "5") (pinfunction "FLAG2_5") (pintype "unspecified"))
    )
    (net (code "57") (name "PANEL_RESET") (class "Default")
      (node (ref "Q2") (pin "1") (pinfunction "G_1") (pintype "unspecified"))
      (node (ref "R9") (pin "1") (pinfunction "1_1") (pintype "input"))
      (node (ref "SJ4") (pin "1") (pinfunction "1_1") (pintype "unspecified"))
    )
    (net (code "58") (name "RESET") (class "Default")
      (node (ref "CN2") (pin "25") (pinfunction "25_25") (pintype "unspecified"))
      (node (ref "Q2") (pin "3") (pinfunction "D_3") (pintype "unspecified"))
      (node (ref "R8") (pin "2") (pinfunction "2_2") (pintype "unspecified"))
    )
    (net (code "59") (name "SCL") (class "Default")
      (node (ref "CN2") (pin "5") (pinfunction "5_5") (pintype "unspecified"))
      (node (ref "FPC1") (pin "3") (pinfunction "3_3") (pintype "unspecified"))
    )
    (net (code "60") (name "SDA") (class "Default")
      (node (ref "CN2") (pin "3") (pinfunction "3_3") (pintype "unspecified"))
      (node (ref "FPC1") (pin "2") (pinfunction "2_2") (pintype "unspecified"))
    )
    (net (code "61") (name "VDDP_EN") (class "Default")
      (node (ref "CN2") (pin "19") (pinfunction "19_19") (pintype "unspecified"))
      (node (ref "R20") (pin "2") (pinfunction "2_2") (pintype "input"))
      (node (ref "SJ1") (pin "2") (pinfunction "2_2") (pintype "unspecified"))
      (node (ref "U7") (pin "4") (pinfunction "FLAG3_4") (pintype "unspecified"))
    )
    (net (code "62") (name "Vin") (class "Default")
      (node (ref "C22") (pin "2") (pinfunction "2_2") (pintype "input"))
      (node (ref "C23") (pin "2") (pinfunction "2_2") (pintype "input"))
      (node (ref "C32") (pin "2") (pinfunction "2_2") (pintype "input"))
      (node (ref "C33") (pin "2") (pinfunction "2_2") (pintype "input"))
      (node (ref "H2") (pin "2") (pinfunction "2_2") (pintype "unspecified"))
      (node (ref "H2") (pin "4") (pinfunction "4_4") (pintype "unspecified"))
      (node (ref "U4") (pin "2") (pinfunction "VIN_2") (pintype "unspecified"))
      (node (ref "U5") (pin "5") (pinfunction "VCC_5") (pintype "unspecified"))
      (node (ref "U6") (pin "2") (pinfunction "VIN_2") (pintype "unspecified"))
      (node (ref "U7") (pin "1") (pinfunction "VCC_1") (pintype "unspecified"))
    )
    (net (code "63") (name "unconnected-(H2-Pad1)") (class "Default")
      (node (ref "H2") (pin "1") (pinfunction "1_1") (pintype "unspecified+no_connect"))
    )
    (net (code "64") (name "unconnected-(H2-Pad3)") (class "Default")
      (node (ref "H2") (pin "3") (pinfunction "3_3") (pintype "unspecified"))
    )
    (net (code "65") (name "unconnected-(H2-Pad5)") (class "Default")
      (node (ref "H2") (pin "5") (pinfunction "5_5") (pintype "unspecified"))
    )
    (net (code "66") (name "unconnected-(H2-Pad7)") (class "Default")
      (node (ref "H2") (pin "7") (pinfunction "7_7") (pintype "unspecified"))
    )
    (net (code "67") (name "unconnected-(H2-Pad8)") (class "Default")
      (node (ref "H2") (pin "8") (pinfunction "8_8") (pintype "unspecified"))
    )
    (net (code "68") (name "unconnected-(H2-Pad10)") (class "Default")
      (node (ref "H2") (pin "10") (pinfunction "10_10") (pintype "unspecified"))
    )
    (net (code "69") (name "unconnected-(H2-Pad11)") (class "Default")
      (node (ref "H2") (pin "11") (pinfunction "11_11") (pintype "unspecified"))
    )
    (net (code "70") (name "unconnected-(H2-Pad12)") (class "Default")
      (node (ref "H2") (pin "12") (pinfunction "12_12") (pintype "unspecified"))
    )
    (net (code "71") (name "unconnected-(H2-Pad13)") (class "Default")
      (node (ref "H2") (pin "13") (pinfunction "13_13") (pintype "unspecified"))
    )
    (net (code "72") (name "unconnected-(H2-Pad15)") (class "Default")
      (node (ref "H2") (pin "15") (pinfunction "15_15") (pintype "unspecified"))
    )
    (net (code "73") (name "unconnected-(H2-Pad16)") (class "Default")
      (node (ref "H2") (pin "16") (pinfunction "16_16") (pintype "unspecified"))
    )
    (net (code "74") (name "unconnected-(H2-Pad17)") (class "Default")
      (node (ref "H2") (pin "17") (pinfunction "17_17") (pintype "unspecified+no_connect"))
    )
    (net (code "75") (name "unconnected-(H2-Pad18)") (class "Default")
      (node (ref "H2") (pin "18") (pinfunction "18_18") (pintype "unspecified"))
    )
    (net (code "76") (name "unconnected-(H2-Pad19)") (class "Default")
      (node (ref "H2") (pin "19") (pinfunction "19_19") (pintype "unspecified"))
    )
    (net (code "77") (name "unconnected-(H2-Pad21)") (class "Default")
      (node (ref "H2") (pin "21") (pinfunction "21_21") (pintype "unspecified"))
    )
    (net (code "78") (name "unconnected-(H2-Pad22)") (class "Default")
      (node (ref "H2") (pin "22") (pinfunction "22_22") (pintype "unspecified"))
    )
    (net (code "79") (name "unconnected-(H2-Pad23)") (class "Default")
      (node (ref "H2") (pin "23") (pinfunction "23_23") (pintype "unspecified"))
    )
    (net (code "80") (name "unconnected-(H2-Pad24)") (class "Default")
      (node (ref "H2") (pin "24") (pinfunction "24_24") (pintype "unspecified"))
    )
    (net (code "81") (name "unconnected-(H2-Pad26)") (class "Default")
      (node (ref "H2") (pin "26") (pinfunction "26_26") (pintype "unspecified"))
    )
    (net (code "82") (name "unconnected-(H2-Pad27)") (class "Default")
      (node (ref "H2") (pin "27") (pinfunction "27_27") (pintype "unspecified"))
    )
    (net (code "83") (name "unconnected-(H2-Pad28)") (class "Default")
      (node (ref "H2") (pin "28") (pinfunction "28_28") (pintype "unspecified"))
    )
    (net (code "84") (name "unconnected-(H2-Pad29)") (class "Default")
      (node (ref "H2") (pin "29") (pinfunction "29_29") (pintype "unspecified"))
    )
    (net (code "85") (name "unconnected-(H2-Pad31)") (class "Default")
      (node (ref "H2") (pin "31") (pinfunction "31_31") (pintype "unspecified"))
    )
    (net (code "86") (name "unconnected-(H2-Pad32)") (class "Default")
      (node (ref "H2") (pin "32") (pinfunction "32_32") (pintype "unspecified"))
    )
    (net (code "87") (name "unconnected-(H2-Pad33)") (class "Default")
      (node (ref "H2") (pin "33") (pinfunction "33_33") (pintype "unspecified"))
    )
    (net (code "88") (name "unconnected-(H2-Pad35)") (class "Default")
      (node (ref "H2") (pin "35") (pinfunction "35_35") (pintype "unspecified"))
    )
    (net (code "89") (name "unconnected-(H2-Pad36)") (class "Default")
      (node (ref "H2") (pin "36") (pinfunction "36_36") (pintype "unspecified"))
    )
    (net (code "90") (name "unconnected-(H2-Pad37)") (class "Default")
      (node (ref "H2") (pin "37") (pinfunction "37_37") (pintype "unspecified"))
    )
    (net (code "91") (name "unconnected-(H2-Pad38)") (class "Default")
      (node (ref "H2") (pin "38") (pinfunction "38_38") (pintype "unspecified"))
    )
    (net (code "92") (name "unconnected-(H2-Pad40)") (class "Default")
      (node (ref "H2") (pin "40") (pinfunction "40_40") (pintype "unspecified"))
    )
    (net (code "93") (name "unconnected-(U1-NC-Pad12)") (class "Default")
      (node (ref "U1") (pin "12") (pinfunction "NC_12") (pintype "unspecified+no_connect"))
    )
    (net (code "94") (name "unconnected-(U1-NC-Pad20)") (class "Default")
      (node (ref "U1") (pin "20") (pinfunction "NC_20") (pintype "unspecified+no_connect"))
    )
    (net (code "95") (name "unconnected-(U2-NC-Pad2)") (class "Default")
      (node (ref "U2") (pin "2") (pinfunction "NC_2") (pintype "unspecified+no_connect"))
    )
    (net (code "96") (name "unconnected-(U2-NC-Pad3)") (class "Default")
      (node (ref "U2") (pin "3") (pinfunction "NC_3") (pintype "unspecified+no_connect"))
    )
    (net (code "97") (name "unconnected-(U4-PG-Pad5)") (class "Default")
      (node (ref "U4") (pin "5") (pinfunction "PG_5") (pintype "unspecified+no_connect"))
    )
    (net (code "98") (name "unconnected-(U5-N.C.-Pad1)") (class "Default")
      (node (ref "U5") (pin "1") (pinfunction "N.C._1") (pintype "unspecified+no_connect"))
    )
    (net (code "99") (name "unconnected-(U6-PG-Pad5)") (class "Default")
      (node (ref "U6") (pin "5") (pinfunction "PG_5") (pintype "unspecified+no_connect"))
    )
  )
)
